# Proximity_Sense.net
KiCad netlist of a schematic drawn in Altium Designer
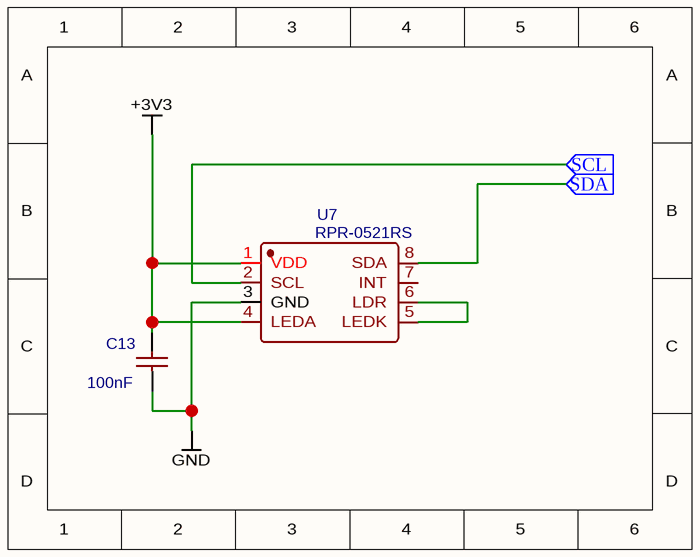
[diagram p0: Proximity_Sense.schdoc]

(export (version "E")
  (design (tool "Eeschema 10.0.6"))
  (components
    (comp (ref "C13")
      (value "100nF")
      (fields
        (field (name "BOM_MANUFACTURER PART") "CL10B104KO8NNNC")
        (field (name "BOM_SUPPLIER PART") "C66501")
      )
      (libsource (lib "altium-import") (part "root_1_100nF_"))
    )
    (comp (ref "U7")
      (value "RPR-0521RS")
      (fields (field (name "BOM_SUPPLIER PART") "C509781") (field (name "CONTRIBUTOR") "LCSC"))
      (libsource (lib "altium-import") (part "root_0_RPR-0521RS_"))
    )
  )
  (nets
    (net (code "1") (name "+3V3") (class "Default")
      (node (ref "C13") (pin "2") (pinfunction "2_2") (pintype "passive"))
      (node (ref "U7") (pin "1") (pinfunction "VDD_1") (pintype "passive"))
      (node (ref "U7") (pin "4") (pinfunction "LEDA_4") (pintype "passive"))
    )
    (net (code "2") (name "/SCL") (class "Default")
      (node (ref "U7") (pin "2") (pinfunction "SCL_2") (pintype "passive"))
    )
    (net (code "3") (name "/SDA") (class "Default")
      (node (ref "U7") (pin "8") (pinfunction "SDA_8") (pintype "passive"))
    )
    (net (code "4") (name "GND") (class "Default")
      (node (ref "C13") (pin "1") (pinfunction "1_1") (pintype "passive"))
      (node (ref "U7") (pin "3") (pinfunction "GND_3") (pintype "passive"))
    )
    (net (code "5") (name "Net-(U7-LDR)") (class "Default")
      (node (ref "U7") (pin "5") (pinfunction "LEDK_5") (pintype "passive"))
      (node (ref "U7") (pin "6") (pinfunction "LDR_6") (pintype "passive"))
    )
    (net (code "6") (name "unconnected-(U7-INT-Pad7)") (class "Default")
      (node (ref "U7") (pin "7") (pinfunction "INT_7") (pintype "passive"))
    )
  )
)
